# Schematic_EmbeddedSystemDesign.net
KiCad netlist of a schematic drawn in Altium Designer
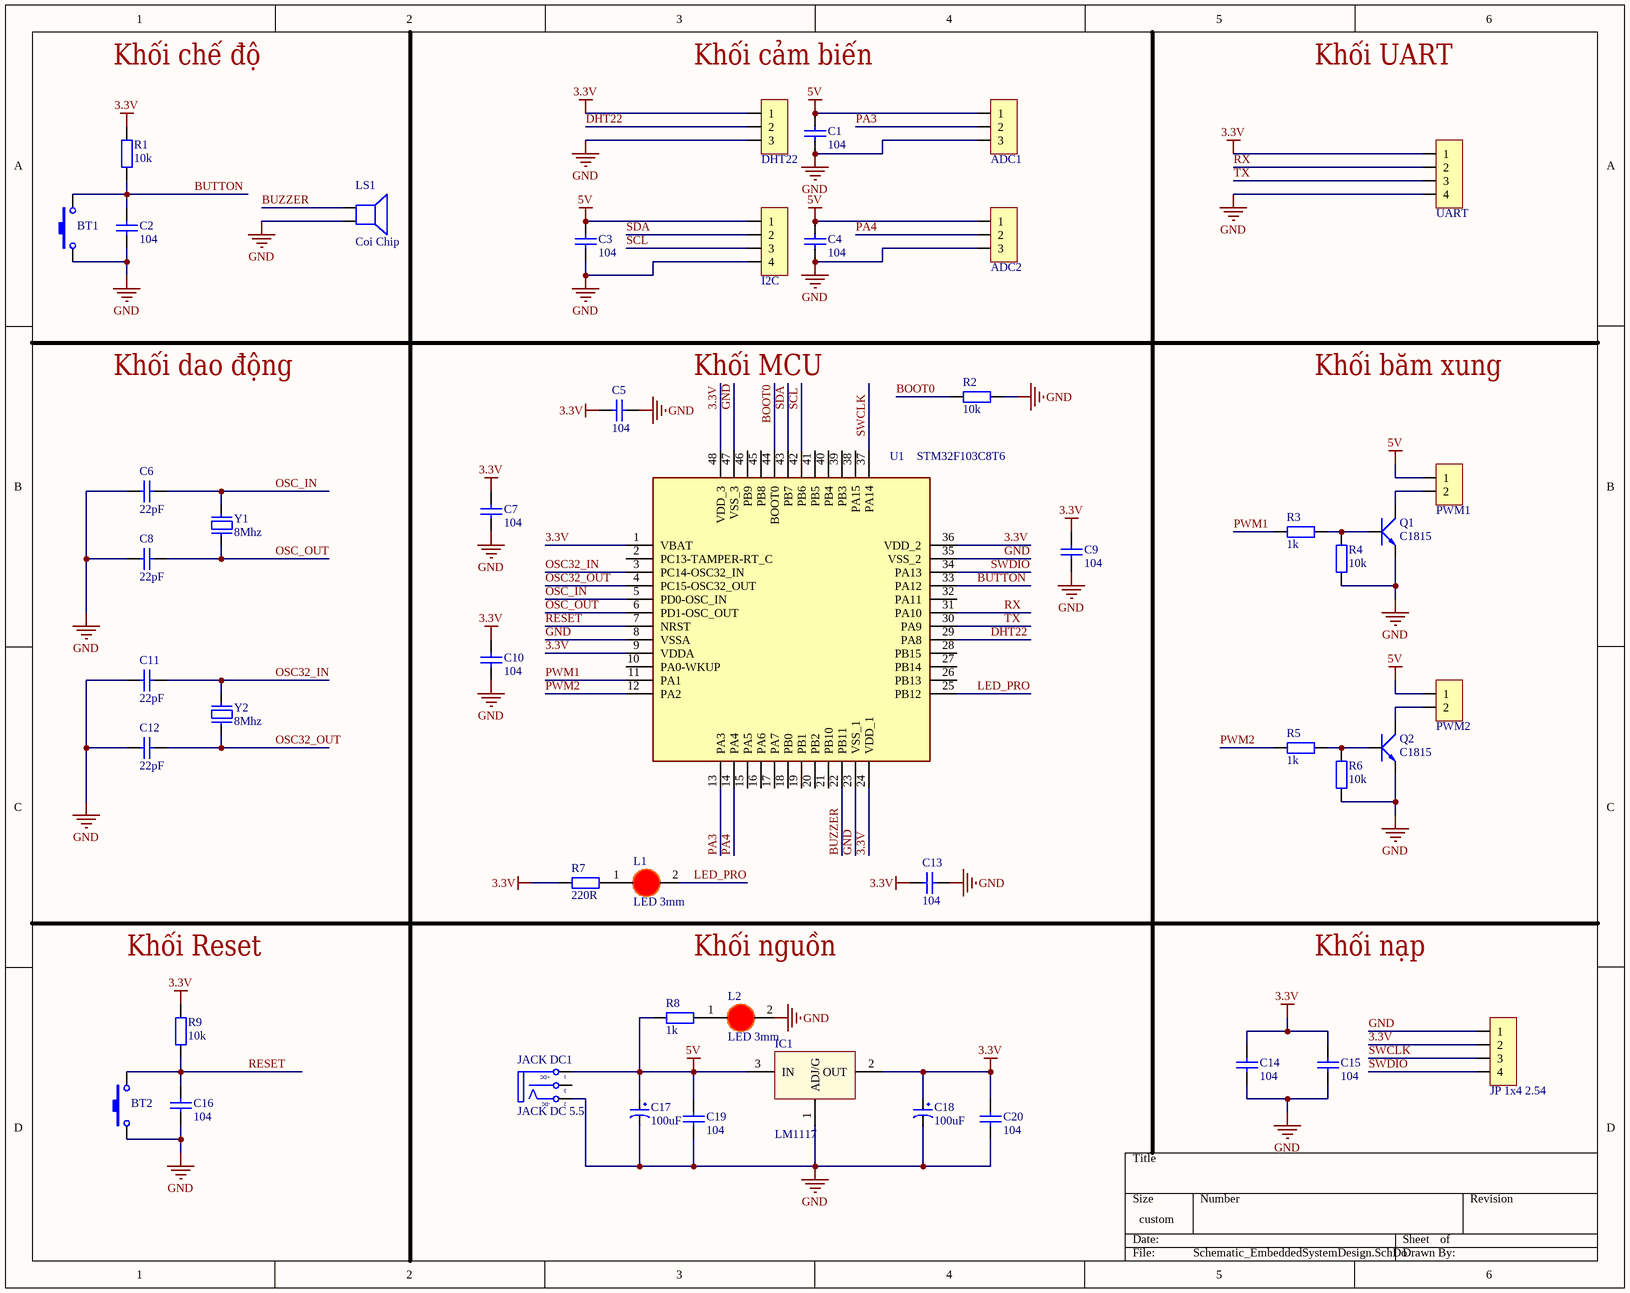
[diagram p0: Schematic_EmbeddedSystemDesign.SchDoc]

(export (version "E")
  (design (tool "Eeschema 10.0.6"))
  (components
    (comp (ref "BT1")
      (value "Nut Nhan 2 Chan SMD 3x6x2.5")
      (footprint "Nut Nhan 2 Chan SMD 3x6x2.5")
      (libsource (lib "Altium_Lib_by_KhueNguyenCreator") (part "Nut Nhan 2 Chan SMD 3x6x2.5"))
    )
    (comp (ref "BT2")
      (value "Nut Nhan 2 Chan SMD 3x6x2.5")
      (footprint "Nut Nhan 2 Chan SMD 3x6x2.5")
      (libsource (lib "Altium_Lib_by_KhueNguyenCreator") (part "Nut Nhan 2 Chan SMD 3x6x2.5"))
    )
    (comp (ref "C1")
      (value "104")
      (footprint "tu gom")
      (description "Cắm")
      (libsource (lib "Altium_Lib_by_KhueNguyenCreator") (part "Tu gom 104 50V"))
    )
    (comp (ref "C2")
      (value "104")
      (footprint "tu gom")
      (description "Cắm")
      (libsource (lib "Altium_Lib_by_KhueNguyenCreator") (part "Tu gom 104 50V"))
    )
    (comp (ref "C3")
      (value "104")
      (footprint "tu gom")
      (description "Cắm")
      (libsource (lib "Altium_Lib_by_KhueNguyenCreator") (part "Tu gom 104 50V"))
    )
    (comp (ref "C4")
      (value "104")
      (footprint "tu gom")
      (description "Cắm")
      (libsource (lib "Altium_Lib_by_KhueNguyenCreator") (part "Tu gom 104 50V"))
    )
    (comp (ref "C5")
      (value "104")
      (footprint "tu gom")
      (description "Cắm")
      (libsource (lib "Altium_Lib_by_KhueNguyenCreator") (part "Tu gom 104 50V"))
    )
    (comp (ref "C6")
      (value "22pF")
      (footprint "tu gom")
      (description "Cắm")
      (libsource (lib "Altium_Lib_by_KhueNguyenCreator") (part "Tu gom 22pF 50V"))
    )
    (comp (ref "C7")
      (value "104")
      (footprint "tu gom")
      (description "Cắm")
      (libsource (lib "Altium_Lib_by_KhueNguyenCreator") (part "Tu gom 104 50V"))
    )
    (comp (ref "C8")
      (value "22pF")
      (footprint "tu gom")
      (description "Cắm")
      (libsource (lib "Altium_Lib_by_KhueNguyenCreator") (part "Tu gom 22pF 50V"))
    )
    (comp (ref "C9")
      (value "104")
      (footprint "tu gom")
      (description "Cắm")
      (libsource (lib "Altium_Lib_by_KhueNguyenCreator") (part "Tu gom 104 50V"))
    )
    (comp (ref "C10")
      (value "104")
      (footprint "tu gom")
      (description "Cắm")
      (libsource (lib "Altium_Lib_by_KhueNguyenCreator") (part "Tu gom 104 50V"))
    )
    (comp (ref "C11")
      (value "22pF")
      (footprint "tu gom")
      (description "Cắm")
      (libsource (lib "Altium_Lib_by_KhueNguyenCreator") (part "Tu gom 22pF 50V"))
    )
    (comp (ref "C12")
      (value "22pF")
      (footprint "tu gom")
      (description "Cắm")
      (libsource (lib "Altium_Lib_by_KhueNguyenCreator") (part "Tu gom 22pF 50V"))
    )
    (comp (ref "C13")
      (value "104")
      (footprint "tu gom")
      (description "Cắm")
      (libsource (lib "Altium_Lib_by_KhueNguyenCreator") (part "Tu gom 104 50V"))
    )
    (comp (ref "C14")
      (value "104")
      (footprint "tu gom")
      (description "Cắm")
      (libsource (lib "Altium_Lib_by_KhueNguyenCreator") (part "Tu gom 104 50V"))
    )
    (comp (ref "C15")
      (value "104")
      (footprint "tu gom")
      (description "Cắm")
      (libsource (lib "Altium_Lib_by_KhueNguyenCreator") (part "Tu gom 104 50V"))
    )
    (comp (ref "C16")
      (value "104")
      (footprint "tu gom")
      (description "Cắm")
      (libsource (lib "Altium_Lib_by_KhueNguyenCreator") (part "Tu gom 104 50V"))
    )
    (comp (ref "C17")
      (value "100uF")
      (footprint "tu hoa 5mm")
      (description "Cắm")
      (libsource (lib "Altium_Lib_by_KhueNguyenCreator") (part "Tu Hoa 100uF 16V 5x11"))
    )
    (comp (ref "C18")
      (value "100uF")
      (footprint "tu hoa 5mm")
      (description "Cắm")
      (libsource (lib "Altium_Lib_by_KhueNguyenCreator") (part "Tu Hoa 100uF 16V 5x11"))
    )
    (comp (ref "C19")
      (value "104")
      (footprint "tu gom")
      (description "Cắm")
      (libsource (lib "Altium_Lib_by_KhueNguyenCreator") (part "Tu gom 104 50V"))
    )
    (comp (ref "C20")
      (value "104")
      (footprint "tu gom")
      (description "Cắm")
      (libsource (lib "Altium_Lib_by_KhueNguyenCreator") (part "Tu gom 104 50V"))
    )
    (comp (ref "IC1")
      (value "LM1117")
      (footprint "SOT223-4N")
      (description "Available in 1.8V, 2.5V, 2.85V, 3.3V, 5V, and  Adjustable Versions")
      (libsource (lib "echipkool-com-library") (part "LM1117"))
    )
    (comp (ref "JACK DC1")
      (value "JACK DC 5.5")
      (footprint "JACK DC 5.5")
      (libsource (lib "Altium_Lib_by_KhueNguyenCreator") (part "JACK DC 5.5"))
    )
    (comp (ref "JP1")
      (value "DHT22")
      (footprint "JP 1x3 DT")
      (description "Cắm")
      (libsource (lib "Altium_Lib_by_KhueNguyenCreator") (part "JP 1x3 2.54 Duc Thang"))
    )
    (comp (ref "JP2")
      (value "ADC1")
      (footprint "JP 1x3 DT")
      (description "Cắm")
      (libsource (lib "Altium_Lib_by_KhueNguyenCreator") (part "JP 1x3 2.54 Duc Thang"))
    )
    (comp (ref "JP3")
      (value "UART")
      (footprint "JP 1x4 DT")
      (description "Cắm")
      (libsource (lib "Altium_Lib_by_KhueNguyenCreator") (part "JP 1x4 2.54 Duc Thang"))
    )
    (comp (ref "JP4")
      (value "I2C")
      (footprint "JP 1x4 DT")
      (description "Cắm")
      (libsource (lib "Altium_Lib_by_KhueNguyenCreator") (part "JP 1x4 2.54 Duc Thang"))
    )
    (comp (ref "JP5")
      (value "ADC2")
      (footprint "JP 1x3 DT")
      (description "Cắm")
      (libsource (lib "Altium_Lib_by_KhueNguyenCreator") (part "JP 1x3 2.54 Duc Thang"))
    )
    (comp (ref "JP6")
      (value "PWM1")
      (footprint "JP 1x2 DT")
      (description "Cắm")
      (libsource (lib "Altium_Lib_by_KhueNguyenCreator") (part "JP 1x2 2.54 Duc Thang"))
    )
    (comp (ref "JP7")
      (value "PWM2")
      (footprint "JP 1x2 DT")
      (description "Cắm")
      (libsource (lib "Altium_Lib_by_KhueNguyenCreator") (part "JP 1x2 2.54 Duc Thang"))
    )
    (comp (ref "JP8")
      (value "JP 1x4 2.54")
      (footprint "JP 1x4 DT")
      (description "Cắm")
      (libsource (lib "Altium_Lib_by_KhueNguyenCreator") (part "JP 1x4 2.54 Duc Thang"))
    )
    (comp (ref "L1")
      (value "LED 3mm")
      (footprint "LED-3MM-RED")
      (description "Cắm")
      (libsource (lib "Altium_Lib_by_KhueNguyenCreator") (part "LED 3mm Do"))
    )
    (comp (ref "L2")
      (value "LED 3mm")
      (footprint "LED-3MM-RED")
      (description "Cắm")
      (libsource (lib "Altium_Lib_by_KhueNguyenCreator") (part "LED 3mm Do"))
    )
    (comp (ref "LS1")
      (value "Coi Chip")
      (footprint "Coi Chip Speacker")
      (description "Còi chip")
      (libsource (lib "Altium_Lib_by_KhueNguyenCreator") (part "Coi Chip Speaker"))
    )
    (comp (ref "Q1")
      (value "C1815")
      (footprint "TO92")
      (description "NPN transistor")
      (libsource (lib "Altium_Lib_by_KhueNguyenCreator") (part "C1815"))
    )
    (comp (ref "Q2")
      (value "C1815")
      (footprint "TO92")
      (description "NPN transistor")
      (libsource (lib "Altium_Lib_by_KhueNguyenCreator") (part "C1815"))
    )
    (comp (ref "R1")
      (value "10k")
      (footprint "tro vach 1/4w")
      (description "Cắm")
      (libsource (lib "Altium_Lib_by_KhueNguyenCreator") (part "Tro Vach 1/4W 1% 10k"))
    )
    (comp (ref "R2")
      (value "10k")
      (footprint "tro vach 1/4w")
      (description "Cắm")
      (libsource (lib "Altium_Lib_by_KhueNguyenCreator") (part "Tro Vach 1/4W 1% 10k"))
    )
    (comp (ref "R3")
      (value "1k")
      (footprint "tro vach 1/4w")
      (description "Cắm")
      (libsource (lib "Altium_Lib_by_KhueNguyenCreator") (part "Tro Vach 1/4W 5% 1k"))
    )
    (comp (ref "R4")
      (value "10k")
      (footprint "tro vach 1/4w")
      (description "Cắm")
      (libsource (lib "Altium_Lib_by_KhueNguyenCreator") (part "Tro Vach 1/4W 1% 10k"))
    )
    (comp (ref "R5")
      (value "1k")
      (footprint "tro vach 1/4w")
      (description "Cắm")
      (libsource (lib "Altium_Lib_by_KhueNguyenCreator") (part "Tro Vach 1/4W 5% 1k"))
    )
    (comp (ref "R6")
      (value "10k")
      (footprint "tro vach 1/4w")
      (description "Cắm")
      (libsource (lib "Altium_Lib_by_KhueNguyenCreator") (part "Tro Vach 1/4W 1% 10k"))
    )
    (comp (ref "R7")
      (value "220R")
      (footprint "tro vach 1/4w")
      (description "Cắm")
      (libsource (lib "Altium_Lib_by_KhueNguyenCreator") (part "Tro Vach 1/4W 5% 220R"))
    )
    (comp (ref "R8")
      (value "1k")
      (footprint "tro vach 1/4w")
      (description "Cắm")
      (libsource (lib "Altium_Lib_by_KhueNguyenCreator") (part "Tro Vach 1/4W 5% 1k"))
    )
    (comp (ref "R9")
      (value "10k")
      (footprint "tro vach 1/4w")
      (description "Cắm")
      (libsource (lib "Altium_Lib_by_KhueNguyenCreator") (part "Tro Vach 1/4W 1% 10k"))
    )
    (comp (ref "U1")
      (value "STM32F103C8T6")
      (footprint "LQFP-48_19.6_393_58X11_SMD")
      (description "ARM® Cortex®-M3 STM32F1 Microcontroller IC 32-Bit 72MHz 64KB (64K x 8) FLASH 48-LQFP (7x7)")
      (fields (field (name "MANUFACTURER") "STMicroelectronics"))
      (libsource (lib "Altium_Lib_by_KhueNguyenCreator") (part "IC_STM32F103C8T6"))
    )
    (comp (ref "Y1")
      (value "8Mhz")
      (footprint "Thach Anh 2 chan cam")
      (description "Crystal For all Crystal 2pin.")
      (libsource (lib "Altium_Lib_by_KhueNguyenCreator") (part "Thach Anh 2 chan Cam"))
    )
    (comp (ref "Y2")
      (value "8Mhz")
      (footprint "Thach Anh 2 chan cam")
      (description "Crystal For all Crystal 2pin.")
      (libsource (lib "Altium_Lib_by_KhueNguyenCreator") (part "Thach Anh 2 chan Cam"))
    )
  )
  (nets
    (net (code "1") (name "/BOOT0") (class "Default")
      (node (ref "R2") (pin "1") (pinfunction "1_1") (pintype "passive"))
      (node (ref "U1") (pin "44") (pinfunction "BOOT0_44") (pintype "passive"))
    )
    (net (code "2") (name "/BUTTON") (class "Default")
      (node (ref "BT1") (pin "2") (pinfunction "2_2") (pintype "passive"))
      (node (ref "C2") (pin "2") (pinfunction "2_2") (pintype "passive"))
      (node (ref "R1") (pin "2") (pinfunction "2_2") (pintype "passive"))
      (node (ref "U1") (pin "33") (pinfunction "PA12_33") (pintype "passive"))
    )
    (net (code "3") (name "/BUZZER") (class "Default")
      (node (ref "LS1") (pin "1") (pinfunction "1_1") (pintype "passive"))
      (node (ref "U1") (pin "22") (pinfunction "PB11_22") (pintype "passive"))
    )
    (net (code "4") (name "/DHT22") (class "Default")
      (node (ref "JP1") (pin "2") (pinfunction "2_2") (pintype "passive"))
      (node (ref "U1") (pin "29") (pinfunction "PA8_29") (pintype "passive"))
    )
    (net (code "5") (name "/LED_PRO") (class "Default")
      (node (ref "L1") (pin "2") (pinfunction "K_2") (pintype "passive"))
      (node (ref "U1") (pin "25") (pinfunction "PB12_25") (pintype "passive"))
    )
    (net (code "6") (name "/OSC32_IN") (class "Default")
      (node (ref "C11") (pin "1") (pinfunction "1_1") (pintype "passive"))
      (node (ref "U1") (pin "3") (pinfunction "PC14-OSC32_IN_3") (pintype "passive"))
      (node (ref "Y2") (pin "2") (pinfunction "2_2") (pintype "passive"))
    )
    (net (code "7") (name "/OSC32_OUT") (class "Default")
      (node (ref "C12") (pin "1") (pinfunction "1_1") (pintype "passive"))
      (node (ref "U1") (pin "4") (pinfunction "PC15-OSC32_OUT_4") (pintype "passive"))
      (node (ref "Y2") (pin "1") (pinfunction "1_1") (pintype "passive"))
    )
    (net (code "8") (name "/OSC_IN") (class "Default")
      (node (ref "C6") (pin "1") (pinfunction "1_1") (pintype "passive"))
      (node (ref "U1") (pin "5") (pinfunction "PD0-OSC_IN_5") (pintype "passive"))
      (node (ref "Y1") (pin "2") (pinfunction "2_2") (pintype "passive"))
    )
    (net (code "9") (name "/OSC_OUT") (class "Default")
      (node (ref "C8") (pin "1") (pinfunction "1_1") (pintype "passive"))
      (node (ref "U1") (pin "6") (pinfunction "PD1-OSC_OUT_6") (pintype "passive"))
      (node (ref "Y1") (pin "1") (pinfunction "1_1") (pintype "passive"))
    )
    (net (code "10") (name "/PA3") (class "Default")
      (node (ref "JP2") (pin "2") (pinfunction "2_2") (pintype "passive"))
      (node (ref "U1") (pin "13") (pinfunction "PA3_13") (pintype "passive"))
    )
    (net (code "11") (name "/PA4") (class "Default")
      (node (ref "JP5") (pin "2") (pinfunction "2_2") (pintype "passive"))
      (node (ref "U1") (pin "14") (pinfunction "PA4_14") (pintype "passive"))
    )
    (net (code "12") (name "/PWM1") (class "Default")
      (node (ref "R3") (pin "1") (pinfunction "1_1") (pintype "passive"))
      (node (ref "U1") (pin "11") (pinfunction "PA1_11") (pintype "passive"))
    )
    (net (code "13") (name "/PWM2") (class "Default")
      (node (ref "R5") (pin "1") (pinfunction "1_1") (pintype "passive"))
      (node (ref "U1") (pin "12") (pinfunction "PA2_12") (pintype "passive"))
    )
    (net (code "14") (name "/RESET") (class "Default")
      (node (ref "BT2") (pin "2") (pinfunction "2_2") (pintype "passive"))
      (node (ref "C16") (pin "2") (pinfunction "2_2") (pintype "passive"))
      (node (ref "R9") (pin "2") (pinfunction "2_2") (pintype "passive"))
      (node (ref "U1") (pin "7") (pinfunction "NRST_7") (pintype "passive"))
    )
    (net (code "15") (name "/RX") (class "Default")
      (node (ref "JP3") (pin "2") (pinfunction "2_2") (pintype "passive"))
      (node (ref "U1") (pin "31") (pinfunction "PA10_31") (pintype "passive"))
    )
    (net (code "16") (name "/SCL") (class "Default")
      (node (ref "JP4") (pin "3") (pinfunction "3_3") (pintype "passive"))
      (node (ref "U1") (pin "42") (pinfunction "PB6_42") (pintype "passive"))
    )
    (net (code "17") (name "/SDA") (class "Default")
      (node (ref "JP4") (pin "2") (pinfunction "2_2") (pintype "passive"))
      (node (ref "U1") (pin "43") (pinfunction "PB7_43") (pintype "passive"))
    )
    (net (code "18") (name "/SWCLK") (class "Default")
      (node (ref "JP8") (pin "3") (pinfunction "3_3") (pintype "passive"))
      (node (ref "U1") (pin "37") (pinfunction "PA14_37") (pintype "passive"))
    )
    (net (code "19") (name "/SWDIO") (class "Default")
      (node (ref "JP8") (pin "4") (pinfunction "4_4") (pintype "passive"))
      (node (ref "U1") (pin "34") (pinfunction "PA13_34") (pintype "passive"))
    )
    (net (code "20") (name "/TX") (class "Default")
      (node (ref "JP3") (pin "3") (pinfunction "3_3") (pintype "passive"))
      (node (ref "U1") (pin "30") (pinfunction "PA9_30") (pintype "passive"))
    )
    (net (code "21") (name "3.3V") (class "Default")
      (node (ref "C10") (pin "1") (pinfunction "1_1") (pintype "passive"))
      (node (ref "C13") (pin "1") (pinfunction "1_1") (pintype "passive"))
      (node (ref "C14") (pin "2") (pinfunction "2_2") (pintype "passive"))
      (node (ref "C15") (pin "2") (pinfunction "2_2") (pintype "passive"))
      (node (ref "C18") (pin "1") (pinfunction "1_1") (pintype "passive"))
      (node (ref "C20") (pin "2") (pinfunction "2_2") (pintype "passive"))
      (node (ref "C5") (pin "1") (pinfunction "1_1") (pintype "passive"))
      (node (ref "C7") (pin "1") (pinfunction "1_1") (pintype "passive"))
      (node (ref "C9") (pin "1") (pinfunction "1_1") (pintype "passive"))
      (node (ref "IC1") (pin "2") (pinfunction "OUT_2") (pintype "passive"))
      (node (ref "JP1") (pin "1") (pinfunction "1_1") (pintype "passive"))
      (node (ref "JP3") (pin "1") (pinfunction "1_1") (pintype "passive"))
      (node (ref "JP8") (pin "2") (pinfunction "2_2") (pintype "passive"))
      (node (ref "R1") (pin "1") (pinfunction "1_1") (pintype "passive"))
      (node (ref "R7") (pin "1") (pinfunction "1_1") (pintype "passive"))
      (node (ref "R9") (pin "1") (pinfunction "1_1") (pintype "passive"))
      (node (ref "U1") (pin "1") (pinfunction "VBAT_1") (pintype "passive"))
      (node (ref "U1") (pin "24") (pinfunction "VDD_1_24") (pintype "passive"))
      (node (ref "U1") (pin "36") (pinfunction "VDD_2_36") (pintype "passive"))
      (node (ref "U1") (pin "48") (pinfunction "VDD_3_48") (pintype "passive"))
      (node (ref "U1") (pin "9") (pinfunction "VDDA_9") (pintype "passive"))
    )
    (net (code "22") (name "5V") (class "Default")
      (node (ref "C1") (pin "1") (pinfunction "1_1") (pintype "passive"))
      (node (ref "C17") (pin "1") (pinfunction "1_1") (pintype "passive"))
      (node (ref "C19") (pin "2") (pinfunction "2_2") (pintype "passive"))
      (node (ref "C3") (pin "1") (pinfunction "1_1") (pintype "passive"))
      (node (ref "C4") (pin "1") (pinfunction "1_1") (pintype "passive"))
      (node (ref "IC1") (pin "3") (pinfunction "IN_3") (pintype "passive"))
      (node (ref "JACK DC1") (pin "1") (pinfunction "T_1") (pintype "passive"))
      (node (ref "JP2") (pin "1") (pinfunction "1_1") (pintype "passive"))
      (node (ref "JP4") (pin "1") (pinfunction "1_1") (pintype "passive"))
      (node (ref "JP5") (pin "1") (pinfunction "1_1") (pintype "passive"))
      (node (ref "JP6") (pin "1") (pinfunction "1_1") (pintype "passive"))
      (node (ref "JP7") (pin "1") (pinfunction "1_1") (pintype "passive"))
      (node (ref "R8") (pin "1") (pinfunction "1_1") (pintype "passive"))
    )
    (net (code "23") (name "GND") (class "Default")
      (node (ref "BT1") (pin "1") (pinfunction "1_1") (pintype "passive"))
      (node (ref "BT2") (pin "1") (pinfunction "1_1") (pintype "passive"))
      (node (ref "C1") (pin "2") (pinfunction "2_2") (pintype "passive"))
      (node (ref "C10") (pin "2") (pinfunction "2_2") (pintype "passive"))
      (node (ref "C11") (pin "2") (pinfunction "2_2") (pintype "passive"))
      (node (ref "C12") (pin "2") (pinfunction "2_2") (pintype "passive"))
      (node (ref "C13") (pin "2") (pinfunction "2_2") (pintype "passive"))
      (node (ref "C14") (pin "1") (pinfunction "1_1") (pintype "passive"))
      (node (ref "C15") (pin "1") (pinfunction "1_1") (pintype "passive"))
      (node (ref "C16") (pin "1") (pinfunction "1_1") (pintype "passive"))
      (node (ref "C17") (pin "2") (pinfunction "2_2") (pintype "passive"))
      (node (ref "C18") (pin "2") (pinfunction "2_2") (pintype "passive"))
      (node (ref "C19") (pin "1") (pinfunction "1_1") (pintype "passive"))
      (node (ref "C2") (pin "1") (pinfunction "1_1") (pintype "passive"))
      (node (ref "C20") (pin "1") (pinfunction "1_1") (pintype "passive"))
      (node (ref "C3") (pin "2") (pinfunction "2_2") (pintype "passive"))
      (node (ref "C4") (pin "2") (pinfunction "2_2") (pintype "passive"))
      (node (ref "C5") (pin "2") (pinfunction "2_2") (pintype "passive"))
      (node (ref "C6") (pin "2") (pinfunction "2_2") (pintype "passive"))
      (node (ref "C7") (pin "2") (pinfunction "2_2") (pintype "passive"))
      (node (ref "C8") (pin "2") (pinfunction "2_2") (pintype "passive"))
      (node (ref "C9") (pin "2") (pinfunction "2_2") (pintype "passive"))
      (node (ref "IC1") (pin "1") (pinfunction "ADJ/G_1") (pintype "passive"))
      (node (ref "JACK DC1") (pin "2") (pinfunction "TN_2") (pintype "passive"))
      (node (ref "JP1") (pin "3") (pinfunction "3_3") (pintype "passive"))
      (node (ref "JP2") (pin "3") (pinfunction "3_3") (pintype "passive"))
      (node (ref "JP3") (pin "4") (pinfunction "4_4") (pintype "passive"))
      (node (ref "JP4") (pin "4") (pinfunction "4_4") (pintype "passive"))
      (node (ref "JP5") (pin "3") (pinfunction "3_3") (pintype "passive"))
      (node (ref "JP8") (pin "1") (pinfunction "1_1") (pintype "passive"))
      (node (ref "L2") (pin "2") (pinfunction "K_2") (pintype "passive"))
      (node (ref "LS1") (pin "2") (pinfunction "2_2") (pintype "passive"))
      (node (ref "Q1") (pin "1") (pinfunction "E_1") (pintype "passive"))
      (node (ref "Q2") (pin "1") (pinfunction "E_1") (pintype "passive"))
      (node (ref "R2") (pin "2") (pinfunction "2_2") (pintype "passive"))
      (node (ref "R4") (pin "2") (pinfunction "2_2") (pintype "passive"))
      (node (ref "R6") (pin "2") (pinfunction "2_2") (pintype "passive"))
      (node (ref "U1") (pin "23") (pinfunction "VSS_1_23") (pintype "passive"))
      (node (ref "U1") (pin "35") (pinfunction "VSS_2_35") (pintype "passive"))
      (node (ref "U1") (pin "47") (pinfunction "VSS_3_47") (pintype "passive"))
      (node (ref "U1") (pin "8") (pinfunction "VSSA_8") (pintype "passive"))
    )
    (net (code "24") (name "Net-(L1-A)") (class "Default")
      (node (ref "L1") (pin "1") (pinfunction "A_1") (pintype "passive"))
      (node (ref "R7") (pin "2") (pinfunction "2_2") (pintype "passive"))
    )
    (net (code "25") (name "Net-(L2-A)") (class "Default")
      (node (ref "L2") (pin "1") (pinfunction "A_1") (pintype "passive"))
      (node (ref "R8") (pin "2") (pinfunction "2_2") (pintype "passive"))
    )
    (net (code "26") (name "Net-(Q1-B)") (class "Default")
      (node (ref "Q1") (pin "3") (pinfunction "B_3") (pintype "passive"))
      (node (ref "R3") (pin "2") (pinfunction "2_2") (pintype "passive"))
      (node (ref "R4") (pin "1") (pinfunction "1_1") (pintype "passive"))
    )
    (net (code "27") (name "Net-(Q1-C)") (class "Default")
      (node (ref "JP6") (pin "2") (pinfunction "2_2") (pintype "passive"))
      (node (ref "Q1") (pin "2") (pinfunction "C_2") (pintype "passive"))
    )
    (net (code "28") (name "Net-(Q2-B)") (class "Default")
      (node (ref "Q2") (pin "3") (pinfunction "B_3") (pintype "passive"))
      (node (ref "R5") (pin "2") (pinfunction "2_2") (pintype "passive"))
      (node (ref "R6") (pin "1") (pinfunction "1_1") (pintype "passive"))
    )
    (net (code "29") (name "Net-(Q2-C)") (class "Default")
      (node (ref "JP7") (pin "2") (pinfunction "2_2") (pintype "passive"))
      (node (ref "Q2") (pin "2") (pinfunction "C_2") (pintype "passive"))
    )
    (net (code "30") (name "unconnected-(JACK DC1-S-Pad3)") (class "Default")
      (node (ref "JACK DC1") (pin "3") (pinfunction "S_3") (pintype "power_in"))
    )
    (net (code "31") (name "unconnected-(U1-PA0-WKUP-Pad10)") (class "Default")
      (node (ref "U1") (pin "10") (pinfunction "PA0-WKUP_10") (pintype "passive"))
    )
    (net (code "32") (name "unconnected-(U1-PA5-Pad15)") (class "Default")
      (node (ref "U1") (pin "15") (pinfunction "PA5_15") (pintype "passive"))
    )
    (net (code "33") (name "unconnected-(U1-PA6-Pad16)") (class "Default")
      (node (ref "U1") (pin "16") (pinfunction "PA6_16") (pintype "passive"))
    )
    (net (code "34") (name "unconnected-(U1-PA7-Pad17)") (class "Default")
      (node (ref "U1") (pin "17") (pinfunction "PA7_17") (pintype "passive"))
    )
    (net (code "35") (name "unconnected-(U1-PA11-Pad32)") (class "Default")
      (node (ref "U1") (pin "32") (pinfunction "PA11_32") (pintype "passive"))
    )
    (net (code "36") (name "unconnected-(U1-PA15-Pad38)") (class "Default")
      (node (ref "U1") (pin "38") (pinfunction "PA15_38") (pintype "passive"))
    )
    (net (code "37") (name "unconnected-(U1-PB0-Pad18)") (class "Default")
      (node (ref "U1") (pin "18") (pinfunction "PB0_18") (pintype "passive"))
    )
    (net (code "38") (name "unconnected-(U1-PB1-Pad19)") (class "Default")
      (node (ref "U1") (pin "19") (pinfunction "PB1_19") (pintype "passive"))
    )
    (net (code "39") (name "unconnected-(U1-PB2-Pad20)") (class "Default")
      (node (ref "U1") (pin "20") (pinfunction "PB2_20") (pintype "passive"))
    )
    (net (code "40") (name "unconnected-(U1-PB3-Pad39)") (class "Default")
      (node (ref "U1") (pin "39") (pinfunction "PB3_39") (pintype "passive"))
    )
    (net (code "41") (name "unconnected-(U1-PB4-Pad40)") (class "Default")
      (node (ref "U1") (pin "40") (pinfunction "PB4_40") (pintype "passive"))
    )
    (net (code "42") (name "unconnected-(U1-PB5-Pad41)") (class "Default")
      (node (ref "U1") (pin "41") (pinfunction "PB5_41") (pintype "passive"))
    )
    (net (code "43") (name "unconnected-(U1-PB8-Pad45)") (class "Default")
      (node (ref "U1") (pin "45") (pinfunction "PB8_45") (pintype "passive"))
    )
    (net (code "44") (name "unconnected-(U1-PB9-Pad46)") (class "Default")
      (node (ref "U1") (pin "46") (pinfunction "PB9_46") (pintype "passive"))
    )
    (net (code "45") (name "unconnected-(U1-PB10-Pad21)") (class "Default")
      (node (ref "U1") (pin "21") (pinfunction "PB10_21") (pintype "passive"))
    )
    (net (code "46") (name "unconnected-(U1-PB13-Pad26)") (class "Default")
      (node (ref "U1") (pin "26") (pinfunction "PB13_26") (pintype "passive"))
    )
    (net (code "47") (name "unconnected-(U1-PB14-Pad27)") (class "Default")
      (node (ref "U1") (pin "27") (pinfunction "PB14_27") (pintype "passive"))
    )
    (net (code "48") (name "unconnected-(U1-PB15-Pad28)") (class "Default")
      (node (ref "U1") (pin "28") (pinfunction "PB15_28") (pintype "passive"))
    )
    (net (code "49") (name "unconnected-(U1-PC13-TAMPER-RT_C-Pad2)") (class "Default")
      (node (ref "U1") (pin "2") (pinfunction "PC13-TAMPER-RT_C_2") (pintype "passive"))
    )
  )
)
